# schema.net
KiCad netlist of a schematic drawn in EAGLE
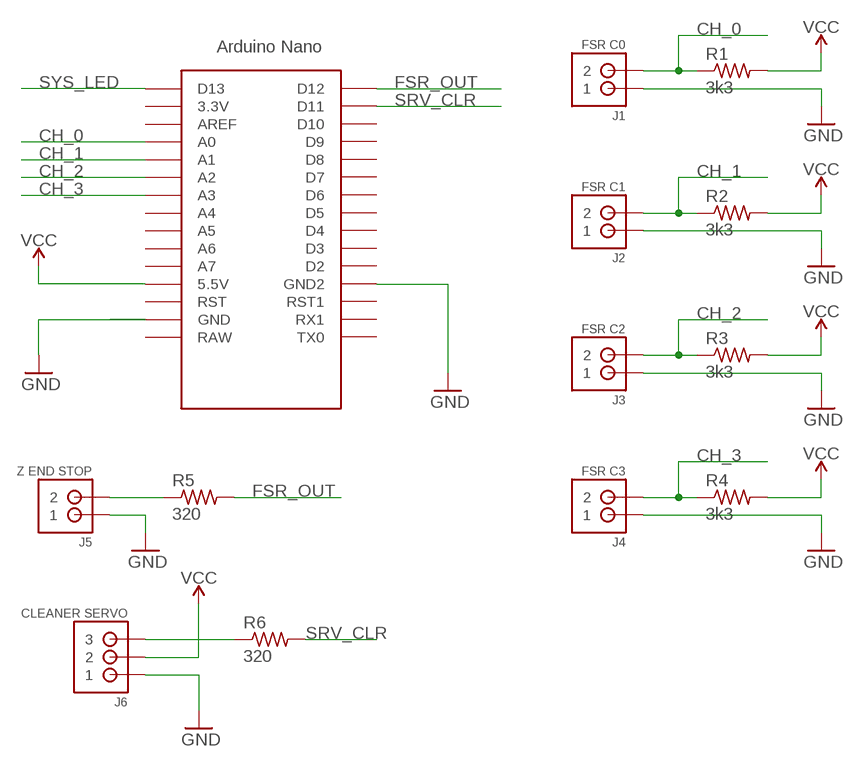
[diagram p0: schematic, sheet 1]

(export (version "E")
  (design (tool "Eeschema 10.0.6"))
  (components
    (comp (ref "J1")
      (value "FSR C0")
      (footprint "eagle-import:JST_B2B-PH_HEADER")
      (libsource (lib "eagle-import") (part "JST-PH_2-PIN_HEADER"))
    )
    (comp (ref "J2")
      (value "FSR C1")
      (footprint "eagle-import:JST_B2B-PH_HEADER")
      (libsource (lib "eagle-import") (part "JST-PH_2-PIN_HEADER"))
    )
    (comp (ref "J3")
      (value "FSR C2")
      (footprint "eagle-import:JST_B2B-PH_HEADER")
      (libsource (lib "eagle-import") (part "JST-PH_2-PIN_HEADER"))
    )
    (comp (ref "J4")
      (value "FSR C3")
      (footprint "eagle-import:JST_B2B-PH_HEADER")
      (libsource (lib "eagle-import") (part "JST-PH_2-PIN_HEADER"))
    )
    (comp (ref "J5")
      (value "Z END STOP")
      (footprint "eagle-import:JST_B2B-PH_HEADER")
      (libsource (lib "eagle-import") (part "JST-PH_2-PIN_HEADER"))
    )
    (comp (ref "J6")
      (value "CLEANER SERVO")
      (footprint "eagle-import:JST_B3B-PH_HEADER")
      (libsource (lib "eagle-import") (part "JST-PH_3-PIN_HEADER"))
    )
    (comp (ref "R1")
      (value "3k3")
      (footprint "eagle-import:0204_5")
      (libsource (lib "eagle-import") (part "R-US_0204/5"))
    )
    (comp (ref "R2")
      (value "3k3")
      (footprint "eagle-import:0204_5")
      (libsource (lib "eagle-import") (part "R-US_0204/5"))
    )
    (comp (ref "R3")
      (value "3k3")
      (footprint "eagle-import:0204_5")
      (libsource (lib "eagle-import") (part "R-US_0204/5"))
    )
    (comp (ref "R4")
      (value "3k3")
      (footprint "eagle-import:0204_5")
      (libsource (lib "eagle-import") (part "R-US_0204/5"))
    )
    (comp (ref "R5")
      (value "320")
      (footprint "eagle-import:0204_5")
      (libsource (lib "eagle-import") (part "R-US_0204/5"))
    )
    (comp (ref "R6")
      (value "320")
      (footprint "eagle-import:0204_5")
      (libsource (lib "eagle-import") (part "R-US_0204/5"))
    )
    (comp (ref "U$1")
      (value "NANO")
      (footprint "eagle-import:NANO")
      (libsource (lib "eagle-import") (part "NANO"))
    )
  )
  (nets
    (net (code "1") (name "/CH_0") (class "Default")
      (node (ref "J1") (pin "P2") (pinfunction "2_P2") (pintype "bidirectional"))
      (node (ref "R1") (pin "1") (pinfunction "1_1") (pintype "passive"))
      (node (ref "U$1") (pin "A0") (pinfunction "A0_A0") (pintype "bidirectional"))
    )
    (net (code "2") (name "/CH_1") (class "Default")
      (node (ref "J2") (pin "P2") (pinfunction "2_P2") (pintype "bidirectional"))
      (node (ref "R2") (pin "1") (pinfunction "1_1") (pintype "passive"))
      (node (ref "U$1") (pin "A1") (pinfunction "A1_A1") (pintype "bidirectional"))
    )
    (net (code "3") (name "/CH_2") (class "Default")
      (node (ref "J3") (pin "P2") (pinfunction "2_P2") (pintype "bidirectional"))
      (node (ref "R3") (pin "1") (pinfunction "1_1") (pintype "passive"))
      (node (ref "U$1") (pin "A2") (pinfunction "A2_A2") (pintype "bidirectional"))
    )
    (net (code "4") (name "/CH_3") (class "Default")
      (node (ref "J4") (pin "P2") (pinfunction "2_P2") (pintype "bidirectional"))
      (node (ref "R4") (pin "1") (pinfunction "1_1") (pintype "passive"))
      (node (ref "U$1") (pin "A3") (pinfunction "A3_A3") (pintype "bidirectional"))
    )
    (net (code "5") (name "/FSR_OUT") (class "Default")
      (node (ref "R5") (pin "2") (pinfunction "2_2") (pintype "passive"))
      (node (ref "U$1") (pin "D12") (pinfunction "D12_D12") (pintype "bidirectional"))
    )
    (net (code "6") (name "/SRV_CLR") (class "Default")
      (node (ref "R6") (pin "2") (pinfunction "2_2") (pintype "passive"))
      (node (ref "U$1") (pin "D11") (pinfunction "D11_D11") (pintype "bidirectional"))
    )
    (net (code "7") (name "/SYS_LED") (class "Default")
      (node (ref "U$1") (pin "D13") (pinfunction "D13_D13") (pintype "bidirectional"))
    )
    (net (code "8") (name "GND") (class "Default")
      (node (ref "J1") (pin "P1") (pinfunction "1_P1") (pintype "bidirectional"))
      (node (ref "J2") (pin "P1") (pinfunction "1_P1") (pintype "bidirectional"))
      (node (ref "J3") (pin "P1") (pinfunction "1_P1") (pintype "bidirectional"))
      (node (ref "J4") (pin "P1") (pinfunction "1_P1") (pintype "bidirectional"))
      (node (ref "J5") (pin "P1") (pinfunction "1_P1") (pintype "bidirectional"))
      (node (ref "J6") (pin "P1") (pinfunction "1_P1") (pintype "bidirectional"))
      (node (ref "U$1") (pin "GND") (pinfunction "GND_GND") (pintype "bidirectional"))
      (node (ref "U$1") (pin "GND1") (pinfunction "GND2_GND1") (pintype "bidirectional"))
    )
    (net (code "9") (name "Net-(J5-2)") (class "Default")
      (node (ref "J5") (pin "P2") (pinfunction "2_P2") (pintype "bidirectional"))
      (node (ref "R5") (pin "1") (pinfunction "1_1") (pintype "passive"))
    )
    (net (code "10") (name "Net-(J6-3)") (class "Default")
      (node (ref "J6") (pin "P3") (pinfunction "3_P3") (pintype "bidirectional"))
      (node (ref "R6") (pin "1") (pinfunction "1_1") (pintype "passive"))
    )
    (net (code "11") (name "VCC") (class "Default")
      (node (ref "J6") (pin "P2") (pinfunction "2_P2") (pintype "bidirectional"))
      (node (ref "R1") (pin "2") (pinfunction "2_2") (pintype "passive"))
      (node (ref "R2") (pin "2") (pinfunction "2_2") (pintype "passive"))
      (node (ref "R3") (pin "2") (pinfunction "2_2") (pintype "passive"))
      (node (ref "R4") (pin "2") (pinfunction "2_2") (pintype "passive"))
      (node (ref "U$1") (pin "5V") (pinfunction "5.5V_5V") (pintype "bidirectional"))
    )
    (net (code "12") (name "unconnected-(U$1-Pad3.3V)") (class "Default")
      (node (ref "U$1") (pin "3.3V") (pinfunction "3.3V_3.3V") (pintype "bidirectional"))
    )
    (net (code "13") (name "unconnected-(U$1-PadA4)") (class "Default")
      (node (ref "U$1") (pin "A4") (pinfunction "A4_A4") (pintype "bidirectional"))
    )
    (net (code "14") (name "unconnected-(U$1-PadA5)") (class "Default")
      (node (ref "U$1") (pin "A5") (pinfunction "A5_A5") (pintype "bidirectional"))
    )
    (net (code "15") (name "unconnected-(U$1-PadA6)") (class "Default")
      (node (ref "U$1") (pin "A6") (pinfunction "A6_A6") (pintype "bidirectional"))
    )
    (net (code "16") (name "unconnected-(U$1-PadA7)") (class "Default")
      (node (ref "U$1") (pin "A7") (pinfunction "A7_A7") (pintype "bidirectional"))
    )
    (net (code "17") (name "unconnected-(U$1-PadAREF)") (class "Default")
      (node (ref "U$1") (pin "AREF") (pinfunction "AREF_AREF") (pintype "bidirectional"))
    )
    (net (code "18") (name "unconnected-(U$1-PadD2)") (class "Default")
      (node (ref "U$1") (pin "D2") (pinfunction "D2_D2") (pintype "bidirectional"))
    )
    (net (code "19") (name "unconnected-(U$1-PadD3)") (class "Default")
      (node (ref "U$1") (pin "D3") (pinfunction "D3_D3") (pintype "bidirectional"))
    )
    (net (code "20") (name "unconnected-(U$1-PadD4)") (class "Default")
      (node (ref "U$1") (pin "D4") (pinfunction "D4_D4") (pintype "bidirectional"))
    )
    (net (code "21") (name "unconnected-(U$1-PadD5)") (class "Default")
      (node (ref "U$1") (pin "D5") (pinfunction "D5_D5") (pintype "bidirectional"))
    )
    (net (code "22") (name "unconnected-(U$1-PadD6)") (class "Default")
      (node (ref "U$1") (pin "D6") (pinfunction "D6_D6") (pintype "bidirectional"))
    )
    (net (code "23") (name "unconnected-(U$1-PadD7)") (class "Default")
      (node (ref "U$1") (pin "D7") (pinfunction "D7_D7") (pintype "bidirectional"))
    )
    (net (code "24") (name "unconnected-(U$1-PadD8)") (class "Default")
      (node (ref "U$1") (pin "D8") (pinfunction "D8_D8") (pintype "bidirectional"))
    )
    (net (code "25") (name "unconnected-(U$1-PadD9)") (class "Default")
      (node (ref "U$1") (pin "D9") (pinfunction "D9_D9") (pintype "bidirectional"))
    )
    (net (code "26") (name "unconnected-(U$1-PadD10)") (class "Default")
      (node (ref "U$1") (pin "D10") (pinfunction "D10_D10") (pintype "bidirectional"))
    )
    (net (code "27") (name "unconnected-(U$1-PadICSP1)") (class "Default")
      (node (ref "U$1") (pin "ICSP1") (pinfunction "ICSP1_ICSP1") (pintype "bidirectional"))
    )
    (net (code "28") (name "unconnected-(U$1-PadICSP2)") (class "Default")
      (node (ref "U$1") (pin "ICSP2") (pinfunction "ICSP2_ICSP2") (pintype "bidirectional"))
    )
    (net (code "29") (name "unconnected-(U$1-PadICSP3)") (class "Default")
      (node (ref "U$1") (pin "ICSP3") (pinfunction "ICSP3_ICSP3") (pintype "bidirectional"))
    )
    (net (code "30") (name "unconnected-(U$1-PadICSP4)") (class "Default")
      (node (ref "U$1") (pin "ICSP4") (pinfunction "ICSP4_ICSP4") (pintype "bidirectional"))
    )
    (net (code "31") (name "unconnected-(U$1-PadICSP5)") (class "Default")
      (node (ref "U$1") (pin "ICSP5") (pinfunction "ICSP5_ICSP5") (pintype "bidirectional"))
    )
    (net (code "32") (name "unconnected-(U$1-PadICSP6)") (class "Default")
      (node (ref "U$1") (pin "ICSP6") (pinfunction "ICSP6_ICSP6") (pintype "bidirectional"))
    )
    (net (code "33") (name "unconnected-(U$1-PadRAW)") (class "Default")
      (node (ref "U$1") (pin "RAW") (pinfunction "RAW_RAW") (pintype "bidirectional"))
    )
    (net (code "34") (name "unconnected-(U$1-PadRST)") (class "Default")
      (node (ref "U$1") (pin "RST") (pinfunction "RST_RST") (pintype "bidirectional"))
    )
    (net (code "35") (name "unconnected-(U$1-PadRST1)") (class "Default")
      (node (ref "U$1") (pin "RST1") (pinfunction "RST1_RST1") (pintype "bidirectional"))
    )
    (net (code "36") (name "unconnected-(U$1-PadRX1)") (class "Default")
      (node (ref "U$1") (pin "RX1") (pinfunction "RX1_RX1") (pintype "bidirectional"))
    )
    (net (code "37") (name "unconnected-(U$1-PadTX0)") (class "Default")
      (node (ref "U$1") (pin "TX0") (pinfunction "TX0_TX0") (pintype "bidirectional"))
    )
  )
)
